# Connectors.net
KiCad netlist of a schematic drawn in Altium Designer
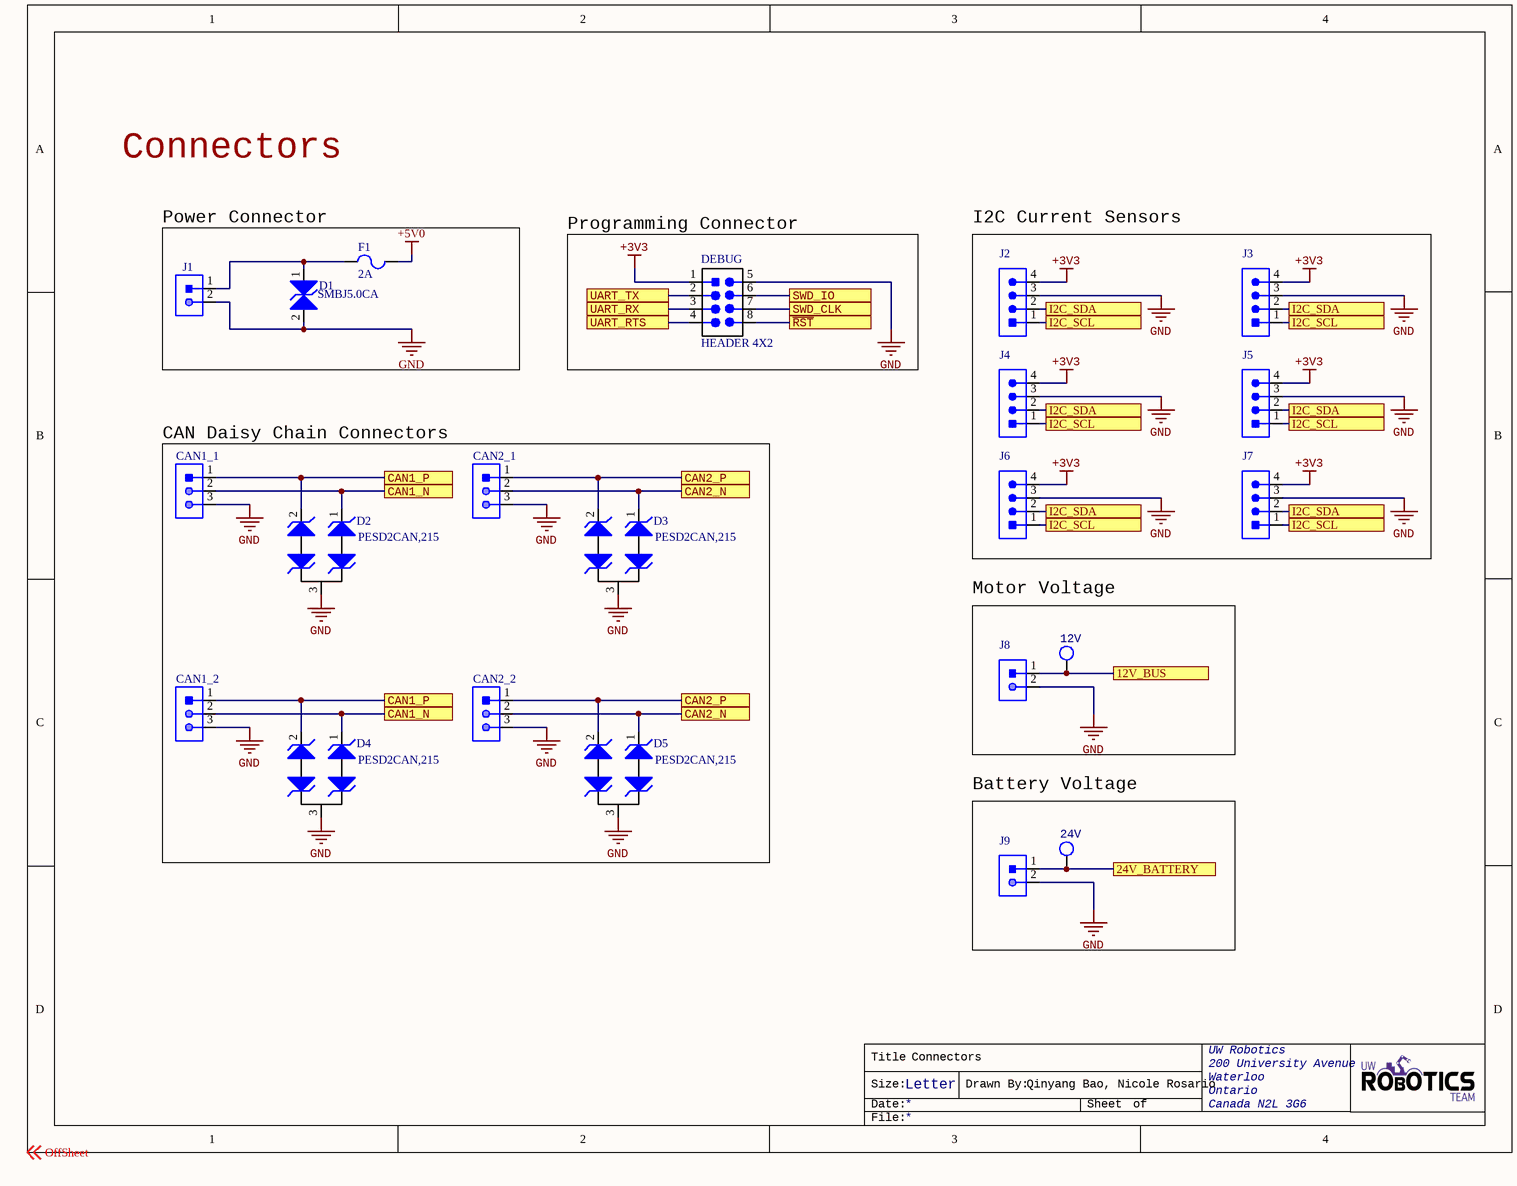
[diagram p0: Connectors.SchDoc]

(export (version "E")
  (design (tool "Eeschema 10.0.6"))
  (components
    (comp (ref "12V")
      (value "TESTPOINT_LOOP")
      (footprint "TESTPOINT_LOOP")
      (description "Loop testpoint through-hole pad")
      (fields (field (name "MANUFACTURER") "Keystone Electronics"))
      (libsource (lib "UWRT_Schematic_Library_2020") (part "TESTPOINT_LOOP"))
    )
    (comp (ref "24V")
      (value "TESTPOINT_LOOP")
      (footprint "TESTPOINT_LOOP")
      (description "Loop testpoint through-hole pad")
      (fields (field (name "MANUFACTURER") "Keystone Electronics"))
      (libsource (lib "UWRT_Schematic_Library_2020") (part "TESTPOINT_LOOP"))
    )
    (comp (ref "CAN1_1")
      (value "CON_3M_SM4")
      (footprint "JST-B3B-SM4-TB")
      (fields
        (field (name "MANUFACTURER") "JST")
        (field (name "MANUFACTURER PART NUMBER") "B3B-PH-SM4-TB(LF)(SN)")
      )
      (libsource (lib "UWRT_Schematic_Library_2020") (part "CON_3M_SM4"))
    )
    (comp (ref "CAN1_2")
      (value "CON_3M_SM4")
      (footprint "JST-B3B-SM4-TB")
      (fields
        (field (name "MANUFACTURER") "JST")
        (field (name "MANUFACTURER PART NUMBER") "B3B-PH-SM4-TB(LF)(SN)")
      )
      (libsource (lib "UWRT_Schematic_Library_2020") (part "CON_3M_SM4"))
    )
    (comp (ref "CAN2_1")
      (value "CON_3M_SM4")
      (footprint "JST-B3B-SM4-TB")
      (fields
        (field (name "MANUFACTURER") "JST")
        (field (name "MANUFACTURER PART NUMBER") "B3B-PH-SM4-TB(LF)(SN)")
      )
      (libsource (lib "UWRT_Schematic_Library_2020") (part "CON_3M_SM4"))
    )
    (comp (ref "CAN2_2")
      (value "CON_3M_SM4")
      (footprint "JST-B3B-SM4-TB")
      (fields
        (field (name "MANUFACTURER") "JST")
        (field (name "MANUFACTURER PART NUMBER") "B3B-PH-SM4-TB(LF)(SN)")
      )
      (libsource (lib "UWRT_Schematic_Library_2020") (part "CON_3M_SM4"))
    )
    (comp (ref "D1")
      (value "TVS_DIODE_BIDIRECTIONAL")
      (footprint "TVS_DIODE_BIDIRECTIONAL")
      (description "TVS DIODE 5V 9.2V DO214AA")
      (fields
        (field (name "MPN") "SMBJ5.0CA")
        (field (name "MANUFACTURER") "Nexperia USA Inc.")
        (field (name "MANUFACTURER PART NUMBER 1") "SMBJ5.0CA")
      )
      (libsource (lib "UWRT_Schematic_Library_2020") (part "TVS_DIODE_BIDIRECTIONAL"))
    )
    (comp (ref "D2")
      (value "TVS_DIODE_CAN")
      (footprint "NXP-SOT323-3")
      (description "TVS DIODE 24V 41V SOT323-3")
      (fields
        (field (name "MANUFACTURER PART NUMBER") "PESD2CAN,215")
        (field (name "MANUFACTURER") "Nexperia USA Inc.")
      )
      (libsource (lib "UWRT_Schematic_Library_2020") (part "TVS_DIODE_CAN"))
    )
    (comp (ref "D3")
      (value "TVS_DIODE_CAN")
      (footprint "NXP-SOT323-3")
      (description "TVS DIODE 24V 41V SOT323-3")
      (fields
        (field (name "MANUFACTURER PART NUMBER") "PESD2CAN,215")
        (field (name "MANUFACTURER") "Nexperia USA Inc.")
      )
      (libsource (lib "UWRT_Schematic_Library_2020") (part "TVS_DIODE_CAN"))
    )
    (comp (ref "D4")
      (value "TVS_DIODE_CAN")
      (footprint "NXP-SOT323-3")
      (description "TVS DIODE 24V 41V SOT323-3")
      (fields
        (field (name "MANUFACTURER PART NUMBER") "PESD2CAN,215")
        (field (name "MANUFACTURER") "Nexperia USA Inc.")
      )
      (libsource (lib "UWRT_Schematic_Library_2020") (part "TVS_DIODE_CAN"))
    )
    (comp (ref "D5")
      (value "TVS_DIODE_CAN")
      (footprint "NXP-SOT323-3")
      (description "TVS DIODE 24V 41V SOT323-3")
      (fields
        (field (name "MANUFACTURER PART NUMBER") "PESD2CAN,215")
        (field (name "MANUFACTURER") "Nexperia USA Inc.")
      )
      (libsource (lib "UWRT_Schematic_Library_2020") (part "TVS_DIODE_CAN"))
    )
    (comp (ref "DEBUG")
      (value "HEADER 4X2")
      (footprint "HEADER_2X4")
      (description "CONN HEADER VERT 8POS 2.54MM")
      (libsource (lib "UWRT_Schematic_Library_2020") (part "HEADER 4X2"))
    )
    (comp (ref "F1")
      (value "FUSE_2A_0603")
      (footprint "FUSE_0603")
      (description "FUSE SMD 2A 32V")
      (fields (field (name "CURRENT RATING") "2A"))
      (libsource (lib "UWRT_Schematic_Library_2020") (part "FUSE_2A_0603"))
    )
    (comp (ref "J1")
      (value "CON_2M_SM4")
      (footprint "JST-B2B-SM4-TB")
      (fields
        (field (name "MANUFACTURER") "JST")
        (field (name "MANUFACTURER PART NUMBER") "B2B-PH-SM4-TB(LF)(SN)")
      )
      (libsource (lib "UWRT_Schematic_Library_2020") (part "CON_2M_SM4"))
    )
    (comp (ref "J2")
      (value "CON_4M_SM4")
      (footprint "JST-B4B-SM4-TB")
      (fields
        (field (name "MANUFACTURER") "JST")
        (field (name "MANUFACTURER PART NUMBER") "B4B-PH-SM4-TB(LF)(SN)")
      )
      (libsource (lib "UWRT_Schematic_Library_2020") (part "CON_4M_SM4"))
    )
    (comp (ref "J3")
      (value "CON_4M_SM4")
      (footprint "JST-B4B-SM4-TB")
      (fields
        (field (name "MANUFACTURER") "JST")
        (field (name "MANUFACTURER PART NUMBER") "B4B-PH-SM4-TB(LF)(SN)")
      )
      (libsource (lib "UWRT_Schematic_Library_2020") (part "CON_4M_SM4"))
    )
    (comp (ref "J4")
      (value "CON_4M_SM4")
      (footprint "JST-B4B-SM4-TB")
      (fields
        (field (name "MANUFACTURER") "JST")
        (field (name "MANUFACTURER PART NUMBER") "B4B-PH-SM4-TB(LF)(SN)")
      )
      (libsource (lib "UWRT_Schematic_Library_2020") (part "CON_4M_SM4"))
    )
    (comp (ref "J5")
      (value "CON_4M_SM4")
      (footprint "JST-B4B-SM4-TB")
      (fields
        (field (name "MANUFACTURER") "JST")
        (field (name "MANUFACTURER PART NUMBER") "B4B-PH-SM4-TB(LF)(SN)")
      )
      (libsource (lib "UWRT_Schematic_Library_2020") (part "CON_4M_SM4"))
    )
    (comp (ref "J6")
      (value "CON_4M_SM4")
      (footprint "JST-B4B-SM4-TB")
      (fields
        (field (name "MANUFACTURER") "JST")
        (field (name "MANUFACTURER PART NUMBER") "B4B-PH-SM4-TB(LF)(SN)")
      )
      (libsource (lib "UWRT_Schematic_Library_2020") (part "CON_4M_SM4"))
    )
    (comp (ref "J7")
      (value "CON_4M_SM4")
      (footprint "JST-B4B-SM4-TB")
      (fields
        (field (name "MANUFACTURER") "JST")
        (field (name "MANUFACTURER PART NUMBER") "B4B-PH-SM4-TB(LF)(SN)")
      )
      (libsource (lib "UWRT_Schematic_Library_2020") (part "CON_4M_SM4"))
    )
    (comp (ref "J8")
      (value "CON_2M_SM4")
      (footprint "JST-B2B-SM4-TB")
      (fields
        (field (name "MANUFACTURER") "JST")
        (field (name "MANUFACTURER PART NUMBER") "B2B-PH-SM4-TB(LF)(SN)")
      )
      (libsource (lib "UWRT_Schematic_Library_2020") (part "CON_2M_SM4"))
    )
    (comp (ref "J9")
      (value "CON_2M_SM4")
      (footprint "JST-B2B-SM4-TB")
      (fields
        (field (name "MANUFACTURER") "JST")
        (field (name "MANUFACTURER PART NUMBER") "B2B-PH-SM4-TB(LF)(SN)")
      )
      (libsource (lib "UWRT_Schematic_Library_2020") (part "CON_2M_SM4"))
    )
  )
  (nets
    (net (code "1") (name "+3V3") (class "Default")
      (node (ref "DEBUG") (pin "1") (pinfunction "VCC_1") (pintype "passive"))
      (node (ref "J2") (pin "4") (pinfunction "4_4") (pintype "passive"))
      (node (ref "J3") (pin "4") (pinfunction "4_4") (pintype "passive"))
      (node (ref "J4") (pin "4") (pinfunction "4_4") (pintype "passive"))
      (node (ref "J5") (pin "4") (pinfunction "4_4") (pintype "passive"))
      (node (ref "J6") (pin "4") (pinfunction "4_4") (pintype "passive"))
      (node (ref "J7") (pin "4") (pinfunction "4_4") (pintype "passive"))
    )
    (net (code "2") (name "+5V0") (class "Default")
      (node (ref "F1") (pin "2") (pinfunction "2_2") (pintype "passive"))
    )
    (net (code "3") (name "/12V_BUS") (class "Default")
      (node (ref "12V") (pin "1") (pintype "passive"))
      (node (ref "J8") (pin "1") (pinfunction "1_1") (pintype "passive"))
    )
    (net (code "4") (name "/24V_BATTERY") (class "Default")
      (node (ref "24V") (pin "1") (pintype "passive"))
      (node (ref "J9") (pin "1") (pinfunction "1_1") (pintype "passive"))
    )
    (net (code "5") (name "/CAN1_N") (class "Default")
      (node (ref "CAN1_1") (pin "2") (pinfunction "2_2") (pintype "passive"))
      (node (ref "CAN1_2") (pin "2") (pinfunction "2_2") (pintype "passive"))
      (node (ref "D2") (pin "1") (pinfunction "1_1") (pintype "passive"))
      (node (ref "D4") (pin "1") (pinfunction "1_1") (pintype "passive"))
    )
    (net (code "6") (name "/CAN1_P") (class "Default")
      (node (ref "CAN1_1") (pin "1") (pinfunction "1_1") (pintype "passive"))
      (node (ref "CAN1_2") (pin "1") (pinfunction "1_1") (pintype "passive"))
      (node (ref "D2") (pin "2") (pinfunction "2_2") (pintype "passive"))
      (node (ref "D4") (pin "2") (pinfunction "2_2") (pintype "passive"))
    )
    (net (code "7") (name "/CAN2_N") (class "Default")
      (node (ref "CAN2_1") (pin "2") (pinfunction "2_2") (pintype "passive"))
      (node (ref "CAN2_2") (pin "2") (pinfunction "2_2") (pintype "passive"))
      (node (ref "D3") (pin "1") (pinfunction "1_1") (pintype "passive"))
      (node (ref "D5") (pin "1") (pinfunction "1_1") (pintype "passive"))
    )
    (net (code "8") (name "/CAN2_P") (class "Default")
      (node (ref "CAN2_1") (pin "1") (pinfunction "1_1") (pintype "passive"))
      (node (ref "CAN2_2") (pin "1") (pinfunction "1_1") (pintype "passive"))
      (node (ref "D3") (pin "2") (pinfunction "2_2") (pintype "passive"))
      (node (ref "D5") (pin "2") (pinfunction "2_2") (pintype "passive"))
    )
    (net (code "9") (name "/I2C_SCL") (class "Default")
      (node (ref "J2") (pin "1") (pinfunction "1_1") (pintype "passive"))
      (node (ref "J3") (pin "1") (pinfunction "1_1") (pintype "passive"))
      (node (ref "J4") (pin "1") (pinfunction "1_1") (pintype "passive"))
      (node (ref "J5") (pin "1") (pinfunction "1_1") (pintype "passive"))
      (node (ref "J6") (pin "1") (pinfunction "1_1") (pintype "passive"))
      (node (ref "J7") (pin "1") (pinfunction "1_1") (pintype "passive"))
    )
    (net (code "10") (name "/I2C_SDA") (class "Default")
      (node (ref "J2") (pin "2") (pinfunction "2_2") (pintype "passive"))
      (node (ref "J3") (pin "2") (pinfunction "2_2") (pintype "passive"))
      (node (ref "J4") (pin "2") (pinfunction "2_2") (pintype "passive"))
      (node (ref "J5") (pin "2") (pinfunction "2_2") (pintype "passive"))
      (node (ref "J6") (pin "2") (pinfunction "2_2") (pintype "passive"))
      (node (ref "J7") (pin "2") (pinfunction "2_2") (pintype "passive"))
    )
    (net (code "11") (name "/SWD_CLK") (class "Default")
      (node (ref "DEBUG") (pin "7") (pinfunction "3_7") (pintype "passive"))
    )
    (net (code "12") (name "/SWD_IO") (class "Default")
      (node (ref "DEBUG") (pin "6") (pinfunction "2_6") (pintype "passive"))
    )
    (net (code "13") (name "/UART_RTS") (class "Default")
      (node (ref "DEBUG") (pin "4") (pinfunction "4_4") (pintype "passive"))
    )
    (net (code "14") (name "/UART_RX") (class "Default")
      (node (ref "DEBUG") (pin "3") (pinfunction "3_3") (pintype "passive"))
    )
    (net (code "15") (name "/UART_TX") (class "Default")
      (node (ref "DEBUG") (pin "2") (pinfunction "2_2") (pintype "passive"))
    )
    (net (code "16") (name "/~{RST}") (class "Default")
      (node (ref "DEBUG") (pin "8") (pinfunction "4_8") (pintype "passive"))
    )
    (net (code "17") (name "GND") (class "Default")
      (node (ref "CAN1_1") (pin "3") (pinfunction "3_3") (pintype "passive"))
      (node (ref "CAN1_2") (pin "3") (pinfunction "3_3") (pintype "passive"))
      (node (ref "CAN2_1") (pin "3") (pinfunction "3_3") (pintype "passive"))
      (node (ref "CAN2_2") (pin "3") (pinfunction "3_3") (pintype "passive"))
      (node (ref "D1") (pin "2") (pinfunction "2_2") (pintype "passive"))
      (node (ref "D2") (pin "3") (pinfunction "3_3") (pintype "passive"))
      (node (ref "D3") (pin "3") (pinfunction "3_3") (pintype "passive"))
      (node (ref "D4") (pin "3") (pinfunction "3_3") (pintype "passive"))
      (node (ref "D5") (pin "3") (pinfunction "3_3") (pintype "passive"))
      (node (ref "DEBUG") (pin "5") (pinfunction "GND_5") (pintype "passive"))
      (node (ref "J1") (pin "2") (pinfunction "2_2") (pintype "passive"))
      (node (ref "J2") (pin "3") (pinfunction "3_3") (pintype "passive"))
      (node (ref "J3") (pin "3") (pinfunction "3_3") (pintype "passive"))
      (node (ref "J4") (pin "3") (pinfunction "3_3") (pintype "passive"))
      (node (ref "J5") (pin "3") (pinfunction "3_3") (pintype "passive"))
      (node (ref "J6") (pin "3") (pinfunction "3_3") (pintype "passive"))
      (node (ref "J7") (pin "3") (pinfunction "3_3") (pintype "passive"))
      (node (ref "J8") (pin "2") (pinfunction "2_2") (pintype "passive"))
      (node (ref "J9") (pin "2") (pinfunction "2_2") (pintype "passive"))
    )
    (net (code "18") (name "Net-(D1-Pad1)") (class "Default")
      (node (ref "D1") (pin "1") (pinfunction "1_1") (pintype "passive"))
      (node (ref "F1") (pin "1") (pinfunction "1_1") (pintype "passive"))
      (node (ref "J1") (pin "1") (pinfunction "1_1") (pintype "passive"))
    )
  )
)
